# cutOffMosfet.net
KiCad netlist of a schematic drawn in EAGLE
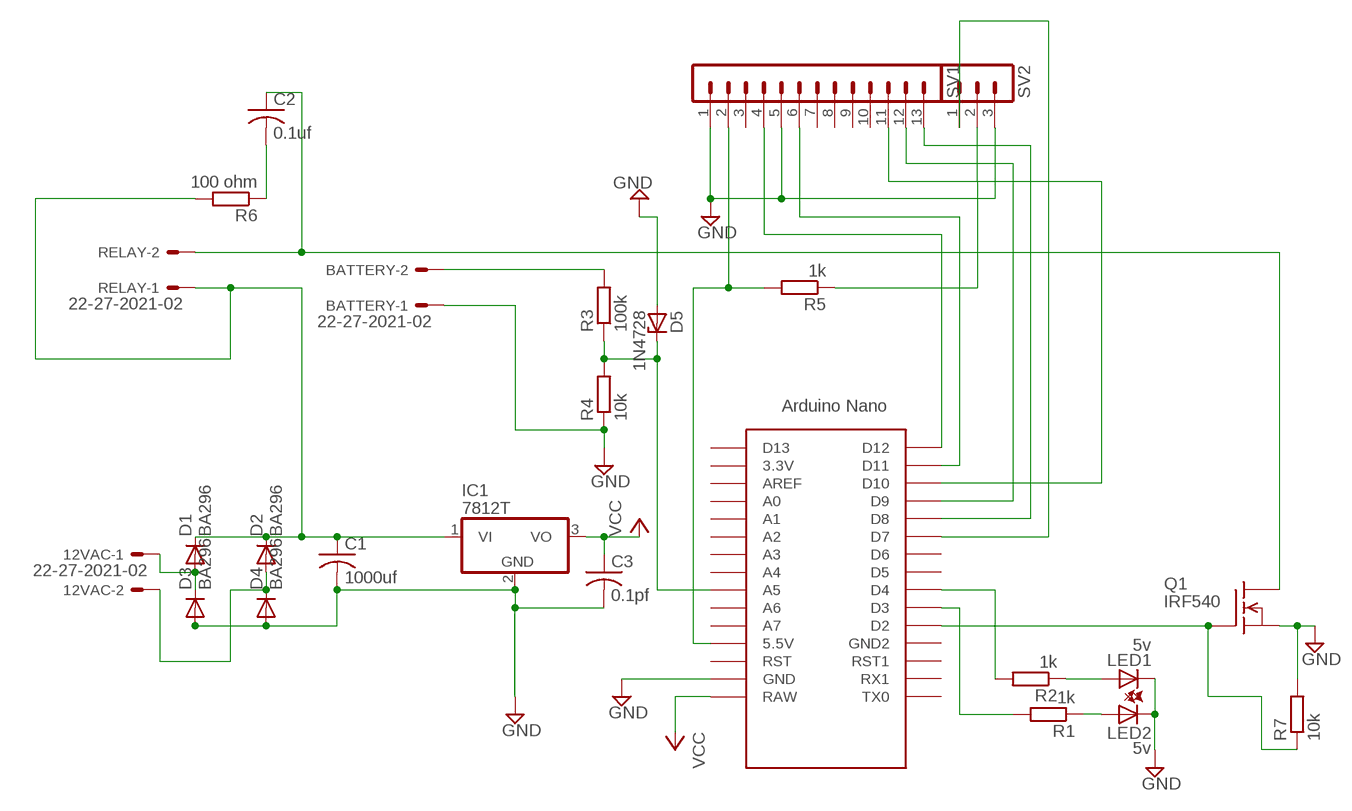
[diagram p0: schematic, sheet 1]

(export (version "E")
  (design (tool "Eeschema 10.0.6"))
  (components
    (comp (ref "12VAC")
      (value "22-27-2021-02")
      (footprint "eagle-import:6410-02")
      (libsource (lib "eagle-import") (part "22-?-0227-2021"))
    )
    (comp (ref "BATTERY")
      (value "22-27-2021-02")
      (footprint "eagle-import:6410-02")
      (libsource (lib "eagle-import") (part "22-?-0227-2021"))
    )
    (comp (ref "C1")
      (value "1000uf")
      (footprint "eagle-import:C050-025X075")
      (libsource (lib "eagle-import") (part "C-US050-025X075"))
    )
    (comp (ref "C2")
      (value "0.1uf")
      (footprint "eagle-import:C050-025X075")
      (libsource (lib "eagle-import") (part "C-US050-025X075"))
    )
    (comp (ref "C3")
      (value "0.1pf")
      (footprint "eagle-import:C050-025X075")
      (libsource (lib "eagle-import") (part "C-US050-025X075"))
    )
    (comp (ref "D1")
      (value "BA296")
      (footprint "eagle-import:P2-15")
      (libsource (lib "eagle-import") (part "BA296"))
    )
    (comp (ref "D2")
      (value "BA296")
      (footprint "eagle-import:P2-15")
      (libsource (lib "eagle-import") (part "BA296"))
    )
    (comp (ref "D3")
      (value "BA296")
      (footprint "eagle-import:P2-15")
      (libsource (lib "eagle-import") (part "BA296"))
    )
    (comp (ref "D4")
      (value "BA296")
      (footprint "eagle-import:P2-15")
      (libsource (lib "eagle-import") (part "BA296"))
    )
    (comp (ref "D5")
      (value "1N4728")
      (footprint "eagle-import:DO41Z10")
      (libsource (lib "eagle-import") (part "1N4728"))
    )
    (comp (ref "IC1")
      (value "7812T")
      (footprint "eagle-import:TO220H")
      (libsource (lib "eagle-import") (part "78T12"))
    )
    (comp (ref "LED1")
      (value "5v")
      (footprint "eagle-import:LED5MM")
      (libsource (lib "eagle-import") (part "LED5MM"))
    )
    (comp (ref "LED2")
      (value "5v")
      (footprint "eagle-import:LED5MM")
      (libsource (lib "eagle-import") (part "LED5MM"))
    )
    (comp (ref "Q1")
      (value "IRF540")
      (footprint "eagle-import:TO220")
      (libsource (lib "eagle-import") (part "IRF540"))
    )
    (comp (ref "R1")
      (value "1k")
      (footprint "eagle-import:0207_10")
      (libsource (lib "eagle-import") (part "R0207/10"))
    )
    (comp (ref "R2")
      (value "1k")
      (footprint "eagle-import:0207_10")
      (libsource (lib "eagle-import") (part "R0207/10"))
    )
    (comp (ref "R3")
      (value "100k")
      (footprint "eagle-import:0207_10")
      (libsource (lib "eagle-import") (part "R0207/10"))
    )
    (comp (ref "R4")
      (value "10k")
      (footprint "eagle-import:0207_10")
      (libsource (lib "eagle-import") (part "R0207/10"))
    )
    (comp (ref "R5")
      (value "1k")
      (footprint "eagle-import:0207_10")
      (libsource (lib "eagle-import") (part "R0207/10"))
    )
    (comp (ref "R6")
      (value "100 ohm")
      (footprint "eagle-import:0207_10")
      (libsource (lib "eagle-import") (part "R0207/10"))
    )
    (comp (ref "R7")
      (value "10k")
      (footprint "eagle-import:0207_10")
      (libsource (lib "eagle-import") (part "R0207/10"))
    )
    (comp (ref "RELAY")
      (value "22-27-2021-02")
      (footprint "eagle-import:6410-02")
      (libsource (lib "eagle-import") (part "22-?-0227-2021"))
    )
    (comp (ref "SV1")
      (value "MA13-1")
      (footprint "eagle-import:MA13-1")
      (libsource (lib "eagle-import") (part "MA13-1"))
    )
    (comp (ref "SV2")
      (value "MA03-1")
      (footprint "eagle-import:MA03-1")
      (libsource (lib "eagle-import") (part "MA03-1"))
    )
    (comp (ref "U$1")
      (value "NANO")
      (footprint "eagle-import:NANO")
      (libsource (lib "eagle-import") (part "NANO"))
    )
  )
  (nets
    (net (code "1") (name "GND") (class "Default")
      (node (ref "BATTERY") (pin "1") (pinfunction "S_1") (pintype "passive"))
      (node (ref "C1") (pin "2") (pinfunction "2_2") (pintype "passive"))
      (node (ref "C3") (pin "2") (pinfunction "2_2") (pintype "passive"))
      (node (ref "D3") (pin "A") (pinfunction "A_A") (pintype "passive"))
      (node (ref "D4") (pin "A") (pinfunction "A_A") (pintype "passive"))
      (node (ref "D5") (pin "A") (pinfunction "A_A") (pintype "passive"))
      (node (ref "IC1") (pin "2") (pinfunction "GND_2") (pintype "passive"))
      (node (ref "LED1") (pin "K") (pinfunction "C_K") (pintype "passive"))
      (node (ref "LED2") (pin "K") (pinfunction "C_K") (pintype "passive"))
      (node (ref "Q1") (pin "3") (pinfunction "S_3") (pintype "passive"))
      (node (ref "R4") (pin "1") (pinfunction "1_1") (pintype "passive"))
      (node (ref "R7") (pin "2") (pinfunction "2_2") (pintype "passive"))
      (node (ref "SV1") (pin "1") (pinfunction "1_1") (pintype "passive"))
      (node (ref "SV1") (pin "5") (pinfunction "5_5") (pintype "passive"))
      (node (ref "SV2") (pin "3") (pinfunction "3_3") (pintype "passive"))
      (node (ref "U$1") (pin "GND") (pinfunction "GND_GND") (pintype "bidirectional"))
    )
    (net (code "2") (name "Net-(12VACA-S)") (class "Default")
      (node (ref "12VAC") (pin "1") (pinfunction "S_1") (pintype "passive"))
      (node (ref "D1") (pin "A") (pinfunction "A_A") (pintype "passive"))
      (node (ref "D3") (pin "C") (pinfunction "C_C") (pintype "passive"))
    )
    (net (code "3") (name "Net-(12VACB-S)") (class "Default")
      (node (ref "12VAC") (pin "2") (pinfunction "S_2") (pintype "passive"))
      (node (ref "D2") (pin "A") (pinfunction "A_A") (pintype "passive"))
      (node (ref "D4") (pin "C") (pinfunction "C_C") (pintype "passive"))
    )
    (net (code "4") (name "Net-(BATTERYB-S)") (class "Default")
      (node (ref "BATTERY") (pin "2") (pinfunction "S_2") (pintype "passive"))
      (node (ref "R3") (pin "2") (pinfunction "2_2") (pintype "passive"))
    )
    (net (code "5") (name "Net-(C2-Pad2)") (class "Default")
      (node (ref "C2") (pin "2") (pinfunction "2_2") (pintype "passive"))
      (node (ref "R6") (pin "1") (pinfunction "1_1") (pintype "passive"))
    )
    (net (code "6") (name "Net-(D5-PadC)") (class "Default")
      (node (ref "D5") (pin "C") (pinfunction "C_C") (pintype "passive"))
      (node (ref "R3") (pin "1") (pinfunction "1_1") (pintype "passive"))
      (node (ref "R4") (pin "2") (pinfunction "2_2") (pintype "passive"))
      (node (ref "U$1") (pin "A5") (pinfunction "A5_A5") (pintype "bidirectional"))
    )
    (net (code "7") (name "Net-(IC1-VI)") (class "Default")
      (node (ref "C1") (pin "1") (pinfunction "1_1") (pintype "passive"))
      (node (ref "D1") (pin "C") (pinfunction "C_C") (pintype "passive"))
      (node (ref "D2") (pin "C") (pinfunction "C_C") (pintype "passive"))
      (node (ref "IC1") (pin "1") (pinfunction "VI_1") (pintype "input"))
      (node (ref "R6") (pin "2") (pinfunction "2_2") (pintype "passive"))
      (node (ref "RELAY") (pin "1") (pinfunction "S_1") (pintype "passive"))
    )
    (net (code "8") (name "Net-(LED1-PadA)") (class "Default")
      (node (ref "LED1") (pin "A") (pinfunction "A_A") (pintype "passive"))
      (node (ref "R2") (pin "1") (pinfunction "1_1") (pintype "passive"))
    )
    (net (code "9") (name "Net-(LED2-PadA)") (class "Default")
      (node (ref "LED2") (pin "A") (pinfunction "A_A") (pintype "passive"))
      (node (ref "R1") (pin "1") (pinfunction "1_1") (pintype "passive"))
    )
    (net (code "10") (name "Net-(Q1-D)") (class "Default")
      (node (ref "C2") (pin "1") (pinfunction "1_1") (pintype "passive"))
      (node (ref "Q1") (pin "2") (pinfunction "D_2") (pintype "passive"))
      (node (ref "RELAY") (pin "2") (pinfunction "S_2") (pintype "passive"))
    )
    (net (code "11") (name "Net-(Q1-G)") (class "Default")
      (node (ref "Q1") (pin "1") (pinfunction "G_1") (pintype "passive"))
      (node (ref "R7") (pin "1") (pinfunction "1_1") (pintype "passive"))
      (node (ref "U$1") (pin "D2") (pinfunction "D2_D2") (pintype "bidirectional"))
    )
    (net (code "12") (name "Net-(R1-Pad2)") (class "Default")
      (node (ref "R1") (pin "2") (pinfunction "2_2") (pintype "passive"))
      (node (ref "U$1") (pin "D3") (pinfunction "D3_D3") (pintype "bidirectional"))
    )
    (net (code "13") (name "Net-(R2-Pad2)") (class "Default")
      (node (ref "R2") (pin "2") (pinfunction "2_2") (pintype "passive"))
      (node (ref "U$1") (pin "D4") (pinfunction "D4_D4") (pintype "bidirectional"))
    )
    (net (code "14") (name "Net-(R5-Pad1)") (class "Default")
      (node (ref "R5") (pin "1") (pinfunction "1_1") (pintype "passive"))
      (node (ref "SV2") (pin "2") (pinfunction "2_2") (pintype "passive"))
    )
    (net (code "15") (name "Net-(SV1-Pad4)") (class "Default")
      (node (ref "SV1") (pin "4") (pinfunction "4_4") (pintype "passive"))
      (node (ref "U$1") (pin "D12") (pinfunction "D12_D12") (pintype "bidirectional"))
    )
    (net (code "16") (name "Net-(SV1-Pad6)") (class "Default")
      (node (ref "SV1") (pin "6") (pinfunction "6_6") (pintype "passive"))
      (node (ref "U$1") (pin "D11") (pinfunction "D11_D11") (pintype "bidirectional"))
    )
    (net (code "17") (name "Net-(SV1-Pad11)") (class "Default")
      (node (ref "SV1") (pin "11") (pinfunction "11_11") (pintype "passive"))
      (node (ref "U$1") (pin "D10") (pinfunction "D10_D10") (pintype "bidirectional"))
    )
    (net (code "18") (name "Net-(SV1-Pad12)") (class "Default")
      (node (ref "SV1") (pin "12") (pinfunction "12_12") (pintype "passive"))
      (node (ref "U$1") (pin "D9") (pinfunction "D9_D9") (pintype "bidirectional"))
    )
    (net (code "19") (name "Net-(SV1-Pad13)") (class "Default")
      (node (ref "SV1") (pin "13") (pinfunction "13_13") (pintype "passive"))
      (node (ref "U$1") (pin "D8") (pinfunction "D8_D8") (pintype "bidirectional"))
    )
    (net (code "20") (name "Net-(SV2-Pad1)") (class "Default")
      (node (ref "SV2") (pin "1") (pinfunction "1_1") (pintype "passive"))
      (node (ref "U$1") (pin "D7") (pinfunction "D7_D7") (pintype "bidirectional"))
    )
    (net (code "21") (name "Net-(U$1-5.5V)") (class "Default")
      (node (ref "R5") (pin "2") (pinfunction "2_2") (pintype "passive"))
      (node (ref "SV1") (pin "2") (pinfunction "2_2") (pintype "passive"))
      (node (ref "U$1") (pin "5V") (pinfunction "5.5V_5V") (pintype "bidirectional"))
    )
    (net (code "22") (name "VCC") (class "Default")
      (node (ref "C3") (pin "1") (pinfunction "1_1") (pintype "passive"))
      (node (ref "IC1") (pin "3") (pinfunction "VO_3") (pintype "passive"))
      (node (ref "U$1") (pin "RAW") (pinfunction "RAW_RAW") (pintype "bidirectional"))
    )
    (net (code "23") (name "unconnected-(SV1-Pad3)") (class "Default")
      (node (ref "SV1") (pin "3") (pinfunction "3_3") (pintype "passive"))
    )
    (net (code "24") (name "unconnected-(SV1-Pad7)") (class "Default")
      (node (ref "SV1") (pin "7") (pinfunction "7_7") (pintype "passive"))
    )
    (net (code "25") (name "unconnected-(SV1-Pad8)") (class "Default")
      (node (ref "SV1") (pin "8") (pinfunction "8_8") (pintype "passive"))
    )
    (net (code "26") (name "unconnected-(SV1-Pad9)") (class "Default")
      (node (ref "SV1") (pin "9") (pinfunction "9_9") (pintype "passive"))
    )
    (net (code "27") (name "unconnected-(SV1-Pad10)") (class "Default")
      (node (ref "SV1") (pin "10") (pinfunction "10_10") (pintype "passive"))
    )
    (net (code "28") (name "unconnected-(U$1-GND2-PadGND1)") (class "Default")
      (node (ref "U$1") (pin "GND1") (pinfunction "GND2_GND1") (pintype "bidirectional"))
    )
    (net (code "29") (name "unconnected-(U$1-Pad3.3V)") (class "Default")
      (node (ref "U$1") (pin "3.3V") (pinfunction "3.3V_3.3V") (pintype "bidirectional"))
    )
    (net (code "30") (name "unconnected-(U$1-PadA0)") (class "Default")
      (node (ref "U$1") (pin "A0") (pinfunction "A0_A0") (pintype "bidirectional"))
    )
    (net (code "31") (name "unconnected-(U$1-PadA1)") (class "Default")
      (node (ref "U$1") (pin "A1") (pinfunction "A1_A1") (pintype "bidirectional"))
    )
    (net (code "32") (name "unconnected-(U$1-PadA2)") (class "Default")
      (node (ref "U$1") (pin "A2") (pinfunction "A2_A2") (pintype "bidirectional"))
    )
    (net (code "33") (name "unconnected-(U$1-PadA3)") (class "Default")
      (node (ref "U$1") (pin "A3") (pinfunction "A3_A3") (pintype "bidirectional"))
    )
    (net (code "34") (name "unconnected-(U$1-PadA4)") (class "Default")
      (node (ref "U$1") (pin "A4") (pinfunction "A4_A4") (pintype "bidirectional"))
    )
    (net (code "35") (name "unconnected-(U$1-PadA6)") (class "Default")
      (node (ref "U$1") (pin "A6") (pinfunction "A6_A6") (pintype "bidirectional"))
    )
    (net (code "36") (name "unconnected-(U$1-PadA7)") (class "Default")
      (node (ref "U$1") (pin "A7") (pinfunction "A7_A7") (pintype "bidirectional"))
    )
    (net (code "37") (name "unconnected-(U$1-PadAREF)") (class "Default")
      (node (ref "U$1") (pin "AREF") (pinfunction "AREF_AREF") (pintype "bidirectional"))
    )
    (net (code "38") (name "unconnected-(U$1-PadD5)") (class "Default")
      (node (ref "U$1") (pin "D5") (pinfunction "D5_D5") (pintype "bidirectional"))
    )
    (net (code "39") (name "unconnected-(U$1-PadD6)") (class "Default")
      (node (ref "U$1") (pin "D6") (pinfunction "D6_D6") (pintype "bidirectional"))
    )
    (net (code "40") (name "unconnected-(U$1-PadD13)") (class "Default")
      (node (ref "U$1") (pin "D13") (pinfunction "D13_D13") (pintype "bidirectional"))
    )
    (net (code "41") (name "unconnected-(U$1-PadICSP1)") (class "Default")
      (node (ref "U$1") (pin "ICSP1") (pinfunction "ICSP1_ICSP1") (pintype "bidirectional"))
    )
    (net (code "42") (name "unconnected-(U$1-PadICSP2)") (class "Default")
      (node (ref "U$1") (pin "ICSP2") (pinfunction "ICSP2_ICSP2") (pintype "bidirectional"))
    )
    (net (code "43") (name "unconnected-(U$1-PadICSP3)") (class "Default")
      (node (ref "U$1") (pin "ICSP3") (pinfunction "ICSP3_ICSP3") (pintype "bidirectional"))
    )
    (net (code "44") (name "unconnected-(U$1-PadICSP4)") (class "Default")
      (node (ref "U$1") (pin "ICSP4") (pinfunction "ICSP4_ICSP4") (pintype "bidirectional"))
    )
    (net (code "45") (name "unconnected-(U$1-PadICSP5)") (class "Default")
      (node (ref "U$1") (pin "ICSP5") (pinfunction "ICSP5_ICSP5") (pintype "bidirectional"))
    )
    (net (code "46") (name "unconnected-(U$1-PadICSP6)") (class "Default")
      (node (ref "U$1") (pin "ICSP6") (pinfunction "ICSP6_ICSP6") (pintype "bidirectional"))
    )
    (net (code "47") (name "unconnected-(U$1-PadRST)") (class "Default")
      (node (ref "U$1") (pin "RST") (pinfunction "RST_RST") (pintype "bidirectional"))
    )
    (net (code "48") (name "unconnected-(U$1-PadRST1)") (class "Default")
      (node (ref "U$1") (pin "RST1") (pinfunction "RST1_RST1") (pintype "bidirectional"))
    )
    (net (code "49") (name "unconnected-(U$1-PadRX1)") (class "Default")
      (node (ref "U$1") (pin "RX1") (pinfunction "RX1_RX1") (pintype "bidirectional"))
    )
    (net (code "50") (name "unconnected-(U$1-PadTX0)") (class "Default")
      (node (ref "U$1") (pin "TX0") (pinfunction "TX0_TX0") (pintype "bidirectional"))
    )
  )
)
